# BEESP_CODE_power.net
KiCad netlist of a schematic drawn in Altium Designer
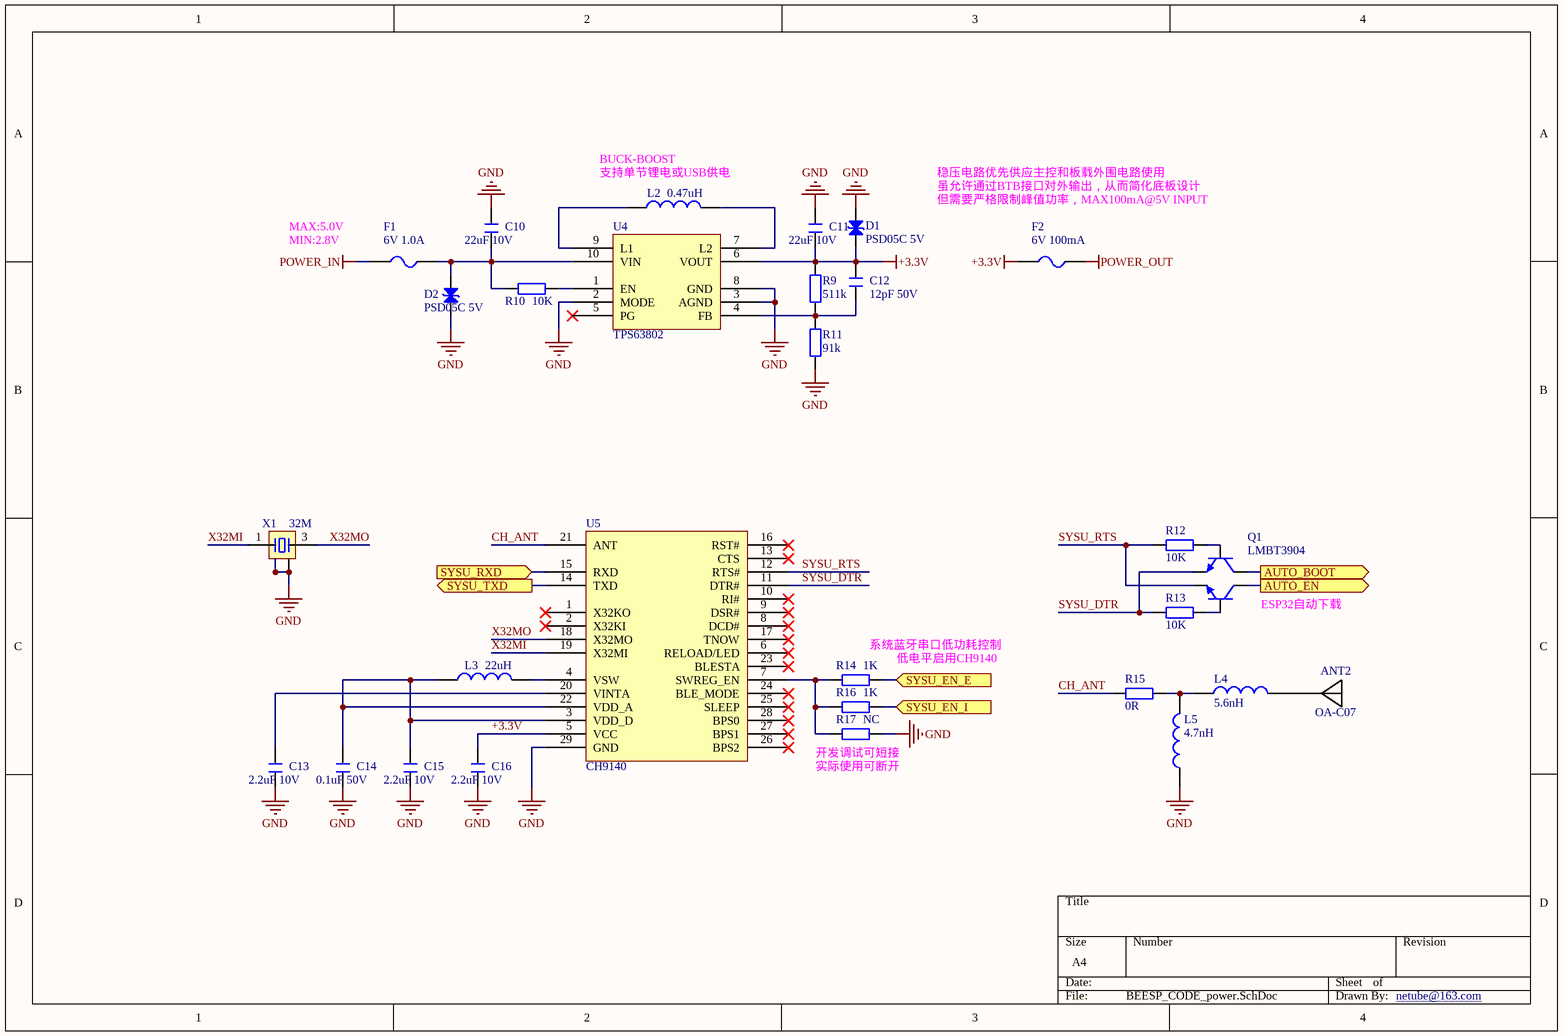
[diagram p0: BEESP_CODE_power.SchDoc]

(export (version "E")
  (design (tool "Eeschema 10.0.6"))
  (components
    (comp (ref "ANT2")
      (value "OA-C07")
      (footprint "OA-C07")
      (description "PCB板载天线")
      (fields (field (name "版权归属") "封装库来自淘宝 ID：黄晶宝石"))
      (libsource (lib "1.8 - WiFi天线-SMA射频座") (part "ANT1"))
    )
    (comp (ref "C10")
      (value "22uF 10V")
      (footprint "C 0603_L")
      (description "贴片电容")
      (libsource (lib "0.1 - 电阻-电容-电感") (part "C"))
    )
    (comp (ref "C11")
      (value "22uF 10V")
      (footprint "C 0603_L")
      (description "贴片电容")
      (libsource (lib "0.1 - 电阻-电容-电感") (part "C"))
    )
    (comp (ref "C12")
      (value "12pF 50V")
      (footprint "C 0402_L")
      (description "贴片电容")
      (libsource (lib "0.1 - 电阻-电容-电感") (part "C"))
    )
    (comp (ref "C13")
      (value "2.2uF 10V")
      (footprint "C 0402_L")
      (description "贴片电容")
      (libsource (lib "0.1 - 电阻-电容-电感") (part "C"))
    )
    (comp (ref "C14")
      (value "0.1uF 50V")
      (footprint "C 0402_L")
      (description "贴片电容")
      (libsource (lib "0.1 - 电阻-电容-电感") (part "C"))
    )
    (comp (ref "C15")
      (value "2.2uF 10V")
      (footprint "C 0402_L")
      (description "贴片电容")
      (libsource (lib "0.1 - 电阻-电容-电感") (part "C"))
    )
    (comp (ref "C16")
      (value "2.2uF 10V")
      (footprint "C 0402_L")
      (description "贴片电容")
      (libsource (lib "0.1 - 电阻-电容-电感") (part "C"))
    )
    (comp (ref "D1")
      (value "PSD05C 5V")
      (footprint "SOD-323")
      (description "TVS保护")
      (libsource (lib "0.2 - 二极管-整流桥") (part "TVS"))
    )
    (comp (ref "D2")
      (value "PSD05C 5V")
      (footprint "SOD-323")
      (description "TVS保护")
      (libsource (lib "0.2 - 二极管-整流桥") (part "TVS"))
    )
    (comp (ref "F1")
      (value "6V 1.0A")
      (footprint "FU 0603")
      (description "贴片保险丝")
      (fields (field (name "版权归属") "封装库来自淘宝卖家 ID：黄晶宝石"))
      (libsource (lib "0.5 - 保险丝-晶振-光耦") (part "FU"))
    )
    (comp (ref "F2")
      (value "6V 100mA")
      (footprint "FU 0603")
      (description "贴片保险丝")
      (fields (field (name "版权归属") "封装库来自淘宝卖家 ID：黄晶宝石"))
      (libsource (lib "0.5 - 保险丝-晶振-光耦") (part "FU"))
    )
    (comp (ref "L2")
      (value "0.47uH")
      (footprint "L 0805")
      (description "小功率贴片电感")
      (libsource (lib "0.1 - 电阻-电容-电感") (part "L"))
    )
    (comp (ref "L3")
      (value "22uH")
      (footprint "R 0402_L")
      (description "小功率贴片电感")
      (libsource (lib "0.1 - 电阻-电容-电感") (part "L"))
    )
    (comp (ref "L4")
      (value "5.6nH")
      (footprint "R 0402_L")
      (description "小功率贴片电感")
      (libsource (lib "0.1 - 电阻-电容-电感") (part "L"))
    )
    (comp (ref "L5")
      (value "4.7nH")
      (footprint "R 0402_L")
      (description "小功率贴片电感")
      (libsource (lib "0.1 - 电阻-电容-电感") (part "L"))
    )
    (comp (ref "Q1")
      (value "LMBT3904")
      (footprint "SOT-363")
      (description "LMBT3904DW1T1G")
      (libsource (lib "0.4 - 三极管-场效应管-可控硅") (part "LMBT3904"))
    )
    (comp (ref "R9")
      (value "511k")
      (footprint "R 0402_L")
      (description "贴片电阻")
      (libsource (lib "0.1 - 电阻-电容-电感") (part "R"))
    )
    (comp (ref "R10")
      (value "10K")
      (footprint "R 0402_L")
      (description "贴片电阻")
      (libsource (lib "0.1 - 电阻-电容-电感") (part "R"))
    )
    (comp (ref "R11")
      (value "91k")
      (footprint "R 0402_L")
      (description "贴片电阻")
      (libsource (lib "0.1 - 电阻-电容-电感") (part "R"))
    )
    (comp (ref "R12")
      (value "10K")
      (footprint "R 0402_L")
      (description "贴片电阻")
      (libsource (lib "0.1 - 电阻-电容-电感") (part "R"))
    )
    (comp (ref "R13")
      (value "10K")
      (footprint "R 0402_L")
      (description "贴片电阻")
      (libsource (lib "0.1 - 电阻-电容-电感") (part "R"))
    )
    (comp (ref "R14")
      (value "1K")
      (footprint "R 0402_L")
      (description "贴片电阻")
      (libsource (lib "0.1 - 电阻-电容-电感") (part "R"))
    )
    (comp (ref "R15")
      (value "0R")
      (footprint "R 0402_L")
      (description "贴片电阻")
      (libsource (lib "0.1 - 电阻-电容-电感") (part "R"))
    )
    (comp (ref "R16")
      (value "1K")
      (footprint "R 0402_L")
      (description "贴片电阻")
      (libsource (lib "0.1 - 电阻-电容-电感") (part "R"))
    )
    (comp (ref "R17")
      (value "NC")
      (footprint "R 0402_L")
      (description "贴片电阻")
      (libsource (lib "0.1 - 电阻-电容-电感") (part "R"))
    )
    (comp (ref "U4")
      (value "TPS63802")
      (footprint "VSON-10_L3.0-W2.0-P0.50-TL")
      (libsource (lib "1.1 - 电源类芯片") (part "TPS63802"))
    )
    (comp (ref "U5")
      (value "CH9140")
      (footprint "QFN28 4*4")
      (libsource (lib "1.9 - CH340系列编程器芯片") (part "CH9140"))
    )
    (comp (ref "X1")
      (value "32M")
      (footprint "OSC 1612-4P")
      (description "4脚无源晶振")
      (fields (field (name "版权归属") "封装库来自淘宝卖家 ID：黄晶宝石"))
      (libsource (lib "0.5 - 保险丝-晶振-光耦") (part "XTAL-4P"))
    )
  )
  (nets
    (net (code "1") (name "+3.3V") (class "Default")
      (node (ref "C11") (pin "1") (pinfunction "1_1") (pintype "passive"))
      (node (ref "C12") (pin "2") (pinfunction "2_2") (pintype "passive"))
      (node (ref "C16") (pin "1") (pinfunction "1_1") (pintype "passive"))
      (node (ref "D1") (pin "2") (pinfunction "K_2") (pintype "passive"))
      (node (ref "F2") (pin "1") (pinfunction "1_1") (pintype "passive"))
      (node (ref "R9") (pin "1") (pinfunction "1_1") (pintype "passive"))
      (node (ref "U4") (pin "6") (pinfunction "VOUT_6") (pintype "passive"))
      (node (ref "U5") (pin "5") (pinfunction "VCC_5") (pintype "passive"))
    )
    (net (code "2") (name "/AUTO_BOOT") (class "Default")
      (node (ref "Q1") (pin "3") (pinfunction "C_3") (pintype "passive"))
    )
    (net (code "3") (name "/AUTO_EN") (class "Default")
      (node (ref "Q1") (pin "6") (pinfunction "C_6") (pintype "passive"))
    )
    (net (code "4") (name "/CH_ANT") (class "Default")
      (node (ref "R15") (pin "1") (pinfunction "1_1") (pintype "passive"))
      (node (ref "U5") (pin "21") (pinfunction "ANT_21") (pintype "passive"))
    )
    (net (code "5") (name "/SYSU_DTR") (class "Default")
      (node (ref "Q1") (pin "4") (pinfunction "E_4") (pintype "passive"))
      (node (ref "R13") (pin "1") (pinfunction "1_1") (pintype "passive"))
      (node (ref "U5") (pin "11") (pinfunction "DTR#_11") (pintype "passive"))
    )
    (net (code "6") (name "/SYSU_EN_E") (class "Default")
      (node (ref "R14") (pin "2") (pinfunction "2_2") (pintype "passive"))
    )
    (net (code "7") (name "/SYSU_EN_I") (class "Default")
      (node (ref "R16") (pin "2") (pinfunction "2_2") (pintype "passive"))
    )
    (net (code "8") (name "/SYSU_RTS") (class "Default")
      (node (ref "Q1") (pin "1") (pinfunction "E_1") (pintype "passive"))
      (node (ref "R12") (pin "1") (pinfunction "1_1") (pintype "passive"))
      (node (ref "U5") (pin "12") (pinfunction "RTS#_12") (pintype "passive"))
    )
    (net (code "9") (name "/SYSU_RXD") (class "Default")
      (node (ref "U5") (pin "15") (pinfunction "RXD_15") (pintype "passive"))
    )
    (net (code "10") (name "/SYSU_TXD") (class "Default")
      (node (ref "U5") (pin "14") (pinfunction "TXD_14") (pintype "passive"))
    )
    (net (code "11") (name "/X32MI") (class "Default")
      (node (ref "U5") (pin "19") (pinfunction "X32MI_19") (pintype "passive"))
      (node (ref "X1") (pin "1") (pinfunction "1_1") (pintype "passive"))
    )
    (net (code "12") (name "/X32MO") (class "Default")
      (node (ref "U5") (pin "18") (pinfunction "X32MO_18") (pintype "passive"))
      (node (ref "X1") (pin "3") (pinfunction "3_3") (pintype "passive"))
    )
    (net (code "13") (name "GND") (class "Default")
      (node (ref "C10") (pin "2") (pinfunction "2_2") (pintype "passive"))
      (node (ref "C11") (pin "2") (pinfunction "2_2") (pintype "passive"))
      (node (ref "C13") (pin "2") (pinfunction "2_2") (pintype "passive"))
      (node (ref "C14") (pin "2") (pinfunction "2_2") (pintype "passive"))
      (node (ref "C15") (pin "2") (pinfunction "2_2") (pintype "passive"))
      (node (ref "C16") (pin "2") (pinfunction "2_2") (pintype "passive"))
      (node (ref "D1") (pin "1") (pinfunction "A_1") (pintype "passive"))
      (node (ref "D2") (pin "1") (pinfunction "A_1") (pintype "passive"))
      (node (ref "L5") (pin "1") (pinfunction "1_1") (pintype "passive"))
      (node (ref "R11") (pin "1") (pinfunction "1_1") (pintype "passive"))
      (node (ref "R17") (pin "2") (pinfunction "2_2") (pintype "passive"))
      (node (ref "U4") (pin "2") (pinfunction "MODE_2") (pintype "passive"))
      (node (ref "U4") (pin "3") (pinfunction "AGND_3") (pintype "passive"))
      (node (ref "U4") (pin "8") (pinfunction "GND_8") (pintype "passive"))
      (node (ref "U5") (pin "29") (pinfunction "GND_29") (pintype "passive"))
      (node (ref "X1") (pin "2") (pinfunction "2_2") (pintype "passive"))
      (node (ref "X1") (pin "4") (pinfunction "4_4") (pintype "passive"))
    )
    (net (code "14") (name "Net-(ANT2-Pad1)") (class "Default")
      (node (ref "ANT2") (pin "1") (pinfunction "1_1") (pintype "passive"))
      (node (ref "L4") (pin "2") (pinfunction "2_2") (pintype "passive"))
    )
    (net (code "15") (name "Net-(D2-K)") (class "Default")
      (node (ref "C10") (pin "1") (pinfunction "1_1") (pintype "passive"))
      (node (ref "D2") (pin "2") (pinfunction "K_2") (pintype "passive"))
      (node (ref "F1") (pin "2") (pinfunction "2_2") (pintype "passive"))
      (node (ref "R10") (pin "1") (pinfunction "1_1") (pintype "passive"))
      (node (ref "U4") (pin "10") (pinfunction "VIN_10") (pintype "passive"))
    )
    (net (code "16") (name "Net-(L4-Pad1)") (class "Default")
      (node (ref "L4") (pin "1") (pinfunction "1_1") (pintype "passive"))
      (node (ref "L5") (pin "2") (pinfunction "2_2") (pintype "passive"))
      (node (ref "R15") (pin "2") (pinfunction "2_2") (pintype "passive"))
    )
    (net (code "17") (name "Net-(Q1-B-Pad2)") (class "Default")
      (node (ref "Q1") (pin "2") (pinfunction "B_2") (pintype "passive"))
      (node (ref "R13") (pin "2") (pinfunction "2_2") (pintype "passive"))
    )
    (net (code "18") (name "Net-(Q1-B-Pad5)") (class "Default")
      (node (ref "Q1") (pin "5") (pinfunction "B_5") (pintype "passive"))
      (node (ref "R12") (pin "2") (pinfunction "2_2") (pintype "passive"))
    )
    (net (code "19") (name "Net-(U4-EN)") (class "Default")
      (node (ref "R10") (pin "2") (pinfunction "2_2") (pintype "passive"))
      (node (ref "U4") (pin "1") (pinfunction "EN_1") (pintype "passive"))
    )
    (net (code "20") (name "Net-(U4-FB)") (class "Default")
      (node (ref "C12") (pin "1") (pinfunction "1_1") (pintype "passive"))
      (node (ref "R11") (pin "2") (pinfunction "2_2") (pintype "passive"))
      (node (ref "R9") (pin "2") (pinfunction "2_2") (pintype "passive"))
      (node (ref "U4") (pin "4") (pinfunction "FB_4") (pintype "passive"))
    )
    (net (code "21") (name "Net-(U4-L1)") (class "Default")
      (node (ref "L2") (pin "1") (pinfunction "1_1") (pintype "passive"))
      (node (ref "U4") (pin "9") (pinfunction "L1_9") (pintype "passive"))
    )
    (net (code "22") (name "Net-(U4-L2)") (class "Default")
      (node (ref "L2") (pin "2") (pinfunction "2_2") (pintype "passive"))
      (node (ref "U4") (pin "7") (pinfunction "L2_7") (pintype "passive"))
    )
    (net (code "23") (name "Net-(U5-SWREG_EN)") (class "Default")
      (node (ref "R14") (pin "1") (pinfunction "1_1") (pintype "passive"))
      (node (ref "R16") (pin "1") (pinfunction "1_1") (pintype "passive"))
      (node (ref "R17") (pin "1") (pinfunction "1_1") (pintype "passive"))
      (node (ref "U5") (pin "7") (pinfunction "SWREG_EN_7") (pintype "passive"))
    )
    (net (code "24") (name "Net-(U5-VDD_A)") (class "Default")
      (node (ref "C14") (pin "1") (pinfunction "1_1") (pintype "passive"))
      (node (ref "C15") (pin "1") (pinfunction "1_1") (pintype "passive"))
      (node (ref "L3") (pin "1") (pinfunction "1_1") (pintype "passive"))
      (node (ref "U5") (pin "22") (pinfunction "VDD_A_22") (pintype "passive"))
      (node (ref "U5") (pin "3") (pinfunction "VDD_D_3") (pintype "passive"))
    )
    (net (code "25") (name "Net-(U5-VINTA)") (class "Default")
      (node (ref "C13") (pin "1") (pinfunction "1_1") (pintype "passive"))
      (node (ref "U5") (pin "20") (pinfunction "VINTA_20") (pintype "passive"))
    )
    (net (code "26") (name "Net-(U5-VSW)") (class "Default")
      (node (ref "L3") (pin "2") (pinfunction "2_2") (pintype "passive"))
      (node (ref "U5") (pin "4") (pinfunction "VSW_4") (pintype "passive"))
    )
    (net (code "27") (name "POWER_IN") (class "Default")
      (node (ref "F1") (pin "1") (pinfunction "1_1") (pintype "passive"))
    )
    (net (code "28") (name "POWER_OUT") (class "Default")
      (node (ref "F2") (pin "2") (pinfunction "2_2") (pintype "passive"))
    )
    (net (code "29") (name "unconnected-(U4-PG-Pad5)") (class "Default")
      (node (ref "U4") (pin "5") (pinfunction "PG_5") (pintype "passive+no_connect"))
    )
    (net (code "30") (name "unconnected-(U5-BLESTA-Pad23)") (class "Default")
      (node (ref "U5") (pin "23") (pinfunction "BLESTA_23") (pintype "passive+no_connect"))
    )
    (net (code "31") (name "unconnected-(U5-BLE_MODE-Pad24)") (class "Default")
      (node (ref "U5") (pin "24") (pinfunction "BLE_MODE_24") (pintype "passive+no_connect"))
    )
    (net (code "32") (name "unconnected-(U5-BPS0-Pad28)") (class "Default")
      (node (ref "U5") (pin "28") (pinfunction "BPS0_28") (pintype "passive+no_connect"))
    )
    (net (code "33") (name "unconnected-(U5-BPS1-Pad27)") (class "Default")
      (node (ref "U5") (pin "27") (pinfunction "BPS1_27") (pintype "passive+no_connect"))
    )
    (net (code "34") (name "unconnected-(U5-BPS2-Pad26)") (class "Default")
      (node (ref "U5") (pin "26") (pinfunction "BPS2_26") (pintype "passive+no_connect"))
    )
    (net (code "35") (name "unconnected-(U5-CTS-Pad13)") (class "Default")
      (node (ref "U5") (pin "13") (pinfunction "CTS_13") (pintype "passive+no_connect"))
    )
    (net (code "36") (name "unconnected-(U5-DCD#-Pad8)") (class "Default")
      (node (ref "U5") (pin "8") (pinfunction "DCD#_8") (pintype "passive+no_connect"))
    )
    (net (code "37") (name "unconnected-(U5-DSR#-Pad9)") (class "Default")
      (node (ref "U5") (pin "9") (pinfunction "DSR#_9") (pintype "passive+no_connect"))
    )
    (net (code "38") (name "unconnected-(U5-RELOAD{slash}LED-Pad6)") (class "Default")
      (node (ref "U5") (pin "6") (pinfunction "RELOAD/LED_6") (pintype "passive+no_connect"))
    )
    (net (code "39") (name "unconnected-(U5-RI#-Pad10)") (class "Default")
      (node (ref "U5") (pin "10") (pinfunction "RI#_10") (pintype "passive+no_connect"))
    )
    (net (code "40") (name "unconnected-(U5-RST#-Pad16)") (class "Default")
      (node (ref "U5") (pin "16") (pinfunction "RST#_16") (pintype "passive+no_connect"))
    )
    (net (code "41") (name "unconnected-(U5-SLEEP-Pad25)") (class "Default")
      (node (ref "U5") (pin "25") (pinfunction "SLEEP_25") (pintype "passive+no_connect"))
    )
    (net (code "42") (name "unconnected-(U5-TNOW-Pad17)") (class "Default")
      (node (ref "U5") (pin "17") (pinfunction "TNOW_17") (pintype "passive+no_connect"))
    )
    (net (code "43") (name "unconnected-(U5-X32KI-Pad2)") (class "Default")
      (node (ref "U5") (pin "2") (pinfunction "X32KI_2") (pintype "passive+no_connect"))
    )
    (net (code "44") (name "unconnected-(U5-X32KO-Pad1)") (class "Default")
      (node (ref "U5") (pin "1") (pinfunction "X32KO_1") (pintype "passive+no_connect"))
    )
  )
)
